# x-OSC_Gloves_v4.net
KiCad netlist of a schematic drawn in EAGLE
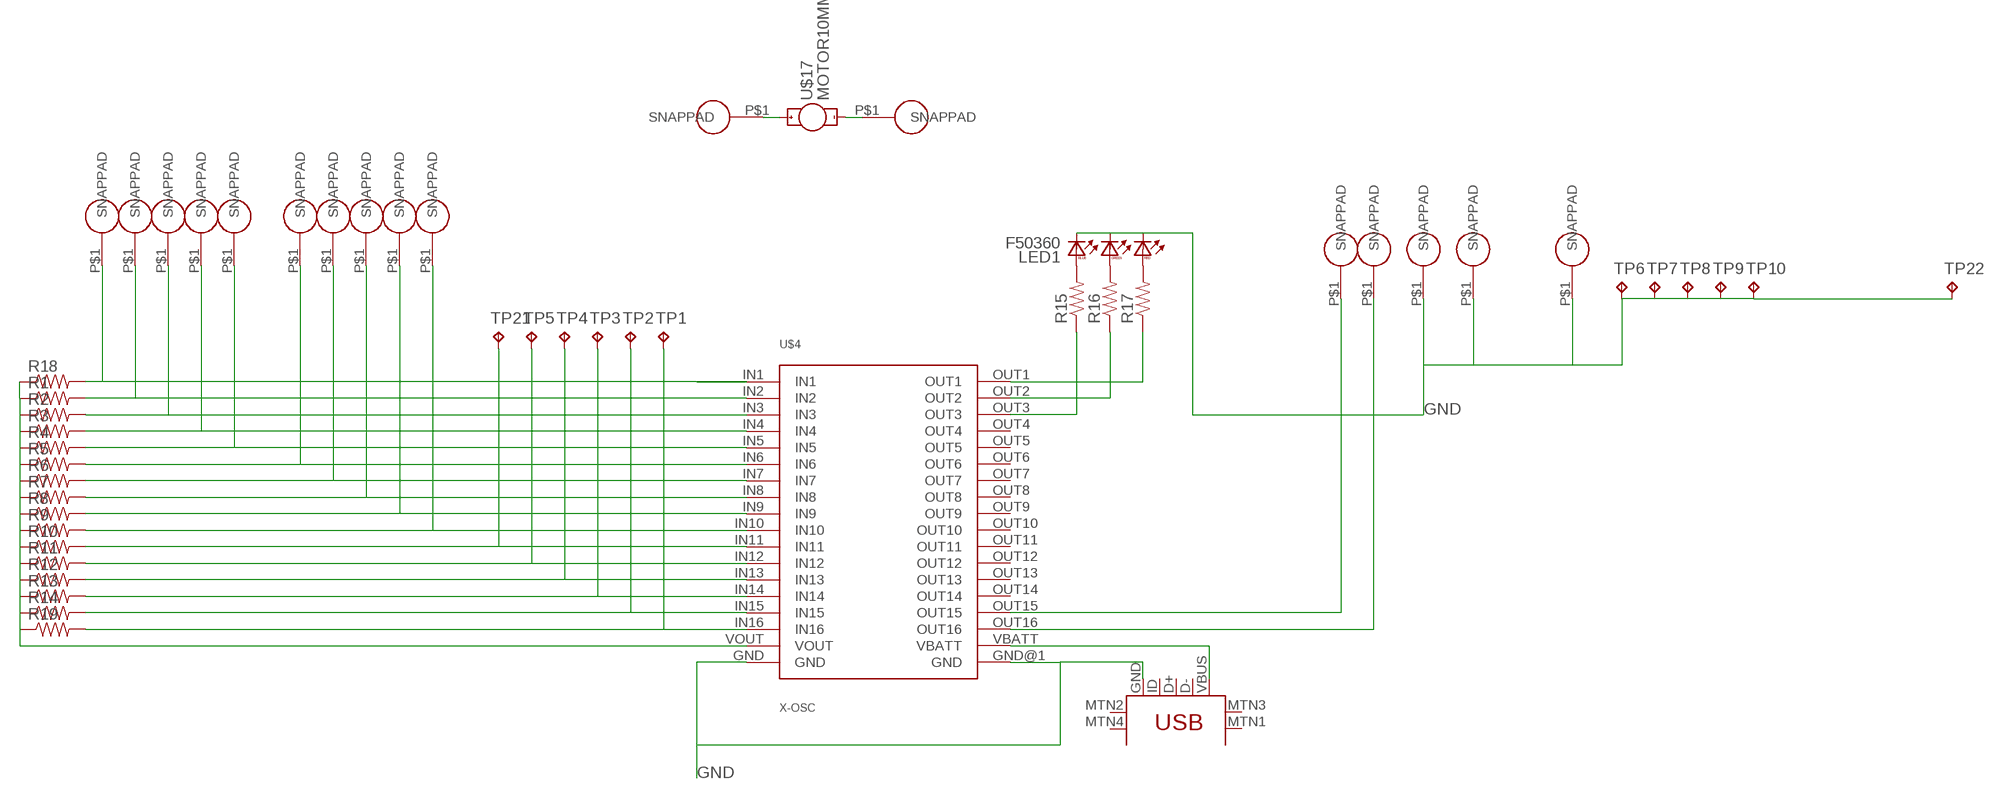
[diagram p0: schematic, sheet 1]

(export (version "E")
  (design (tool "Eeschema 10.0.6"))
  (components
    (comp (ref "LED1")
      (value "F50360")
      (footprint "eagle-import:F50360")
      (libsource (lib "eagle-import") (part "F50360"))
    )
    (comp (ref "R1")
      (value "RESISTOR0805-RES")
      (footprint "eagle-import:0805")
      (libsource (lib "eagle-import") (part "RESISTOR0805-RES"))
    )
    (comp (ref "R2")
      (value "RESISTOR0805-RES")
      (footprint "eagle-import:0805")
      (libsource (lib "eagle-import") (part "RESISTOR0805-RES"))
    )
    (comp (ref "R3")
      (value "RESISTOR0805-RES")
      (footprint "eagle-import:0805")
      (libsource (lib "eagle-import") (part "RESISTOR0805-RES"))
    )
    (comp (ref "R4")
      (value "RESISTOR0805-RES")
      (footprint "eagle-import:0805")
      (libsource (lib "eagle-import") (part "RESISTOR0805-RES"))
    )
    (comp (ref "R5")
      (value "RESISTOR0805-RES")
      (footprint "eagle-import:0805")
      (libsource (lib "eagle-import") (part "RESISTOR0805-RES"))
    )
    (comp (ref "R6")
      (value "RESISTOR0805-RES")
      (footprint "eagle-import:0805")
      (libsource (lib "eagle-import") (part "RESISTOR0805-RES"))
    )
    (comp (ref "R7")
      (value "RESISTOR0805-RES")
      (footprint "eagle-import:0805")
      (libsource (lib "eagle-import") (part "RESISTOR0805-RES"))
    )
    (comp (ref "R8")
      (value "RESISTOR0805-RES")
      (footprint "eagle-import:0805")
      (libsource (lib "eagle-import") (part "RESISTOR0805-RES"))
    )
    (comp (ref "R9")
      (value "RESISTOR0805-RES")
      (footprint "eagle-import:0805")
      (libsource (lib "eagle-import") (part "RESISTOR0805-RES"))
    )
    (comp (ref "R10")
      (value "RESISTOR0805-RES")
      (footprint "eagle-import:0805")
      (libsource (lib "eagle-import") (part "RESISTOR0805-RES"))
    )
    (comp (ref "R11")
      (value "RESISTOR0805-RES")
      (footprint "eagle-import:0805")
      (libsource (lib "eagle-import") (part "RESISTOR0805-RES"))
    )
    (comp (ref "R12")
      (value "RESISTOR0805-RES")
      (footprint "eagle-import:0805")
      (libsource (lib "eagle-import") (part "RESISTOR0805-RES"))
    )
    (comp (ref "R13")
      (value "RESISTOR0805-RES")
      (footprint "eagle-import:0805")
      (libsource (lib "eagle-import") (part "RESISTOR0805-RES"))
    )
    (comp (ref "R14")
      (value "RESISTOR0805-RES")
      (footprint "eagle-import:0805")
      (libsource (lib "eagle-import") (part "RESISTOR0805-RES"))
    )
    (comp (ref "R15")
      (value "RESISTOR0805-RES")
      (footprint "eagle-import:0805")
      (libsource (lib "eagle-import") (part "RESISTOR0805-RES"))
    )
    (comp (ref "R16")
      (value "RESISTOR0805-RES")
      (footprint "eagle-import:0805")
      (libsource (lib "eagle-import") (part "RESISTOR0805-RES"))
    )
    (comp (ref "R17")
      (value "RESISTOR0805-RES")
      (footprint "eagle-import:0805")
      (libsource (lib "eagle-import") (part "RESISTOR0805-RES"))
    )
    (comp (ref "R18")
      (value "RESISTOR0805-RES")
      (footprint "eagle-import:0805")
      (libsource (lib "eagle-import") (part "RESISTOR0805-RES"))
    )
    (comp (ref "R19")
      (value "RESISTOR0805-RES")
      (footprint "eagle-import:0805")
      (libsource (lib "eagle-import") (part "RESISTOR0805-RES"))
    )
    (comp (ref "TP1")
      (value "TPTP20R")
      (footprint "eagle-import:TP20R")
      (libsource (lib "eagle-import") (part "TPTP20R"))
    )
    (comp (ref "TP2")
      (value "TPTP20R")
      (footprint "eagle-import:TP20R")
      (libsource (lib "eagle-import") (part "TPTP20R"))
    )
    (comp (ref "TP3")
      (value "TPTP20R")
      (footprint "eagle-import:TP20R")
      (libsource (lib "eagle-import") (part "TPTP20R"))
    )
    (comp (ref "TP4")
      (value "TPTP20R")
      (footprint "eagle-import:TP20R")
      (libsource (lib "eagle-import") (part "TPTP20R"))
    )
    (comp (ref "TP5")
      (value "TPTP20R")
      (footprint "eagle-import:TP20R")
      (libsource (lib "eagle-import") (part "TPTP20R"))
    )
    (comp (ref "TP6")
      (value "TPTP20R")
      (footprint "eagle-import:TP20R")
      (libsource (lib "eagle-import") (part "TPTP20R"))
    )
    (comp (ref "TP7")
      (value "TPTP20R")
      (footprint "eagle-import:TP20R")
      (libsource (lib "eagle-import") (part "TPTP20R"))
    )
    (comp (ref "TP8")
      (value "TPTP20R")
      (footprint "eagle-import:TP20R")
      (libsource (lib "eagle-import") (part "TPTP20R"))
    )
    (comp (ref "TP9")
      (value "TPTP20R")
      (footprint "eagle-import:TP20R")
      (libsource (lib "eagle-import") (part "TPTP20R"))
    )
    (comp (ref "TP10")
      (value "TPTP20R")
      (footprint "eagle-import:TP20R")
      (libsource (lib "eagle-import") (part "TPTP20R"))
    )
    (comp (ref "TP21")
      (value "TPTP20R")
      (footprint "eagle-import:TP20R")
      (libsource (lib "eagle-import") (part "TPTP20R"))
    )
    (comp (ref "TP22")
      (value "TPTP20R")
      (footprint "eagle-import:TP20R")
      (libsource (lib "eagle-import") (part "TPTP20R"))
    )
    (comp (ref "U$1")
      (value "SNAP-PAD_7MM_ROUND")
      (footprint "eagle-import:SNAP-PAD_7MM_RD")
      (libsource (lib "eagle-import") (part "SNAP-PAD_7MM_ROUND"))
    )
    (comp (ref "U$2")
      (value "SNAP-PAD_7MM_ROUND")
      (footprint "eagle-import:SNAP-PAD_7MM_RD")
      (libsource (lib "eagle-import") (part "SNAP-PAD_7MM_ROUND"))
    )
    (comp (ref "U$3")
      (value "SNAP-PAD_7MM_ROUND")
      (footprint "eagle-import:SNAP-PAD_7MM_RD")
      (libsource (lib "eagle-import") (part "SNAP-PAD_7MM_ROUND"))
    )
    (comp (ref "U$4")
      (value "X-OSC")
      (footprint "eagle-import:X-OSC_SMD")
      (libsource (lib "eagle-import") (part "X-OSC"))
    )
    (comp (ref "U$5")
      (value "USB-MINIB-5PIN")
      (footprint "eagle-import:USB-MINIB")
      (libsource (lib "eagle-import") (part "USB-MINIB-5PIN"))
    )
    (comp (ref "U$6")
      (value "SNAP-PAD_7MM_ROUND")
      (footprint "eagle-import:SNAP-PAD_7MM_RD")
      (libsource (lib "eagle-import") (part "SNAP-PAD_7MM_ROUND"))
    )
    (comp (ref "U$7")
      (value "SNAP-PAD_7MM_ROUND")
      (footprint "eagle-import:SNAP-PAD_7MM_RD")
      (libsource (lib "eagle-import") (part "SNAP-PAD_7MM_ROUND"))
    )
    (comp (ref "U$8")
      (value "SNAP-PAD_7MM_ROUND")
      (footprint "eagle-import:SNAP-PAD_7MM_RD")
      (libsource (lib "eagle-import") (part "SNAP-PAD_7MM_ROUND"))
    )
    (comp (ref "U$9")
      (value "SNAP-PAD_7MM_ROUND")
      (footprint "eagle-import:SNAP-PAD_7MM_RD")
      (libsource (lib "eagle-import") (part "SNAP-PAD_7MM_ROUND"))
    )
    (comp (ref "U$10")
      (value "SNAP-PAD_7MM_ROUND")
      (footprint "eagle-import:SNAP-PAD_7MM_RD")
      (libsource (lib "eagle-import") (part "SNAP-PAD_7MM_ROUND"))
    )
    (comp (ref "U$11")
      (value "SNAP-PAD_7MM_ROUND")
      (footprint "eagle-import:SNAP-PAD_7MM_RD")
      (libsource (lib "eagle-import") (part "SNAP-PAD_7MM_ROUND"))
    )
    (comp (ref "U$13")
      (value "SNAP-PAD_7MM_ROUND")
      (footprint "eagle-import:SNAP-PAD_7MM_RD")
      (libsource (lib "eagle-import") (part "SNAP-PAD_7MM_ROUND"))
    )
    (comp (ref "U$14")
      (value "SNAP-PAD_7MM_ROUND")
      (footprint "eagle-import:SNAP-PAD_7MM_RD")
      (libsource (lib "eagle-import") (part "SNAP-PAD_7MM_ROUND"))
    )
    (comp (ref "U$15")
      (value "SNAP-PAD_7MM_ROUND")
      (footprint "eagle-import:SNAP-PAD_7MM_RD")
      (libsource (lib "eagle-import") (part "SNAP-PAD_7MM_ROUND"))
    )
    (comp (ref "U$16")
      (value "SNAP-PAD_7MM_ROUND")
      (footprint "eagle-import:SNAP-PAD_7MM_RD")
      (libsource (lib "eagle-import") (part "SNAP-PAD_7MM_ROUND"))
    )
    (comp (ref "U$17")
      (value "MOTOR10MM")
      (footprint "eagle-import:VIBE-MOTOR-10MM")
      (libsource (lib "eagle-import") (part "MOTOR10MM"))
    )
    (comp (ref "U$18")
      (value "SNAP-PAD_7MM_ROUND")
      (footprint "eagle-import:SNAP-PAD_7MM_RD")
      (libsource (lib "eagle-import") (part "SNAP-PAD_7MM_ROUND"))
    )
    (comp (ref "U$19")
      (value "SNAP-PAD_7MM_ROUND")
      (footprint "eagle-import:SNAP-PAD_7MM_RD")
      (libsource (lib "eagle-import") (part "SNAP-PAD_7MM_ROUND"))
    )
    (comp (ref "U$20")
      (value "SNAP-PAD_7MM_ROUND")
      (footprint "eagle-import:SNAP-PAD_7MM_RD")
      (libsource (lib "eagle-import") (part "SNAP-PAD_7MM_ROUND"))
    )
    (comp (ref "U$21")
      (value "SNAP-PAD_7MM_ROUND")
      (footprint "eagle-import:SNAP-PAD_7MM_RD")
      (libsource (lib "eagle-import") (part "SNAP-PAD_7MM_ROUND"))
    )
  )
  (nets
    (net (code "1") (name "/GND") (class "Default")
      (node (ref "LED1") (pin "BC") (pinfunction "BC_BC") (pintype "passive"))
      (node (ref "LED1") (pin "GC") (pinfunction "GC_GC") (pintype "passive"))
      (node (ref "LED1") (pin "RC") (pinfunction "RC_RC") (pintype "passive"))
      (node (ref "TP10") (pin "TP") (pinfunction "TP_TP") (pintype "input"))
      (node (ref "TP22") (pin "TP") (pinfunction "TP_TP") (pintype "input"))
      (node (ref "TP6") (pin "TP") (pinfunction "TP_TP") (pintype "input"))
      (node (ref "TP7") (pin "TP") (pinfunction "TP_TP") (pintype "input"))
      (node (ref "TP8") (pin "TP") (pinfunction "TP_TP") (pintype "input"))
      (node (ref "TP9") (pin "TP") (pinfunction "TP_TP") (pintype "input"))
      (node (ref "U$15") (pin "P$1") (pinfunction "SNAPPAD_P$1") (pintype "bidirectional"))
      (node (ref "U$16") (pin "P$1") (pinfunction "SNAPPAD_P$1") (pintype "bidirectional"))
      (node (ref "U$18") (pin "P$1") (pinfunction "SNAPPAD_P$1") (pintype "bidirectional"))
      (node (ref "U$4") (pin "GND") (pinfunction "GND_GND") (pintype "bidirectional"))
      (node (ref "U$4") (pin "GND@1") (pinfunction "GND_GND@1") (pintype "bidirectional"))
      (node (ref "U$5") (pin "GND") (pinfunction "GND_GND") (pintype "bidirectional"))
    )
    (net (code "2") (name "Net-(LED1-PadBA)") (class "Default")
      (node (ref "LED1") (pin "BA") (pinfunction "BA_BA") (pintype "passive"))
      (node (ref "R15") (pin "2") (pinfunction "2_2") (pintype "passive"))
    )
    (net (code "3") (name "Net-(LED1-PadGA)") (class "Default")
      (node (ref "LED1") (pin "GA") (pinfunction "GA_GA") (pintype "passive"))
      (node (ref "R16") (pin "2") (pinfunction "2_2") (pintype "passive"))
    )
    (net (code "4") (name "Net-(LED1-PadRA)") (class "Default")
      (node (ref "LED1") (pin "RA") (pinfunction "RA_RA") (pintype "passive"))
      (node (ref "R17") (pin "2") (pinfunction "2_2") (pintype "passive"))
    )
    (net (code "5") (name "Net-(R1-Pad1)") (class "Default")
      (node (ref "R1") (pin "1") (pinfunction "1_1") (pintype "passive"))
      (node (ref "R10") (pin "1") (pinfunction "1_1") (pintype "passive"))
      (node (ref "R11") (pin "1") (pinfunction "1_1") (pintype "passive"))
      (node (ref "R12") (pin "1") (pinfunction "1_1") (pintype "passive"))
      (node (ref "R13") (pin "1") (pinfunction "1_1") (pintype "passive"))
      (node (ref "R14") (pin "1") (pinfunction "1_1") (pintype "passive"))
      (node (ref "R18") (pin "1") (pinfunction "1_1") (pintype "passive"))
      (node (ref "R19") (pin "1") (pinfunction "1_1") (pintype "passive"))
      (node (ref "R2") (pin "1") (pinfunction "1_1") (pintype "passive"))
      (node (ref "R3") (pin "1") (pinfunction "1_1") (pintype "passive"))
      (node (ref "R4") (pin "1") (pinfunction "1_1") (pintype "passive"))
      (node (ref "R5") (pin "1") (pinfunction "1_1") (pintype "passive"))
      (node (ref "R6") (pin "1") (pinfunction "1_1") (pintype "passive"))
      (node (ref "R7") (pin "1") (pinfunction "1_1") (pintype "passive"))
      (node (ref "R8") (pin "1") (pinfunction "1_1") (pintype "passive"))
      (node (ref "R9") (pin "1") (pinfunction "1_1") (pintype "passive"))
      (node (ref "U$4") (pin "VOUT") (pinfunction "VOUT_VOUT") (pintype "bidirectional"))
    )
    (net (code "6") (name "Net-(R10-Pad2)") (class "Default")
      (node (ref "R10") (pin "2") (pinfunction "2_2") (pintype "passive"))
      (node (ref "TP21") (pin "TP") (pinfunction "TP_TP") (pintype "input"))
      (node (ref "U$4") (pin "IN11") (pinfunction "IN11_IN11") (pintype "bidirectional"))
    )
    (net (code "7") (name "Net-(R11-Pad2)") (class "Default")
      (node (ref "R11") (pin "2") (pinfunction "2_2") (pintype "passive"))
      (node (ref "TP5") (pin "TP") (pinfunction "TP_TP") (pintype "input"))
      (node (ref "U$4") (pin "IN12") (pinfunction "IN12_IN12") (pintype "bidirectional"))
    )
    (net (code "8") (name "Net-(R12-Pad2)") (class "Default")
      (node (ref "R12") (pin "2") (pinfunction "2_2") (pintype "passive"))
      (node (ref "TP4") (pin "TP") (pinfunction "TP_TP") (pintype "input"))
      (node (ref "U$4") (pin "IN13") (pinfunction "IN13_IN13") (pintype "bidirectional"))
    )
    (net (code "9") (name "Net-(R13-Pad2)") (class "Default")
      (node (ref "R13") (pin "2") (pinfunction "2_2") (pintype "passive"))
      (node (ref "TP3") (pin "TP") (pinfunction "TP_TP") (pintype "input"))
      (node (ref "U$4") (pin "IN14") (pinfunction "IN14_IN14") (pintype "bidirectional"))
    )
    (net (code "10") (name "Net-(R14-Pad2)") (class "Default")
      (node (ref "R14") (pin "2") (pinfunction "2_2") (pintype "passive"))
      (node (ref "TP2") (pin "TP") (pinfunction "TP_TP") (pintype "input"))
      (node (ref "U$4") (pin "IN15") (pinfunction "IN15_IN15") (pintype "bidirectional"))
    )
    (net (code "11") (name "Net-(R15-Pad1)") (class "Default")
      (node (ref "R15") (pin "1") (pinfunction "1_1") (pintype "passive"))
      (node (ref "U$4") (pin "OUT3") (pinfunction "OUT3_OUT3") (pintype "bidirectional"))
    )
    (net (code "12") (name "Net-(R16-Pad1)") (class "Default")
      (node (ref "R16") (pin "1") (pinfunction "1_1") (pintype "passive"))
      (node (ref "U$4") (pin "OUT2") (pinfunction "OUT2_OUT2") (pintype "bidirectional"))
    )
    (net (code "13") (name "Net-(R17-Pad1)") (class "Default")
      (node (ref "R17") (pin "1") (pinfunction "1_1") (pintype "passive"))
      (node (ref "U$4") (pin "OUT1") (pinfunction "OUT1_OUT1") (pintype "bidirectional"))
    )
    (net (code "14") (name "Net-(R19-Pad2)") (class "Default")
      (node (ref "R19") (pin "2") (pinfunction "2_2") (pintype "passive"))
      (node (ref "TP1") (pin "TP") (pinfunction "TP_TP") (pintype "input"))
      (node (ref "U$4") (pin "IN16") (pinfunction "IN16_IN16") (pintype "bidirectional"))
    )
    (net (code "15") (name "Net-(U$1-SNAPPAD)") (class "Default")
      (node (ref "R1") (pin "2") (pinfunction "2_2") (pintype "passive"))
      (node (ref "U$1") (pin "P$1") (pinfunction "SNAPPAD_P$1") (pintype "bidirectional"))
      (node (ref "U$4") (pin "IN2") (pinfunction "IN2_IN2") (pintype "bidirectional"))
    )
    (net (code "16") (name "Net-(U$2-SNAPPAD)") (class "Default")
      (node (ref "R2") (pin "2") (pinfunction "2_2") (pintype "passive"))
      (node (ref "U$2") (pin "P$1") (pinfunction "SNAPPAD_P$1") (pintype "bidirectional"))
      (node (ref "U$4") (pin "IN3") (pinfunction "IN3_IN3") (pintype "bidirectional"))
    )
    (net (code "17") (name "Net-(U$3-SNAPPAD)") (class "Default")
      (node (ref "R3") (pin "2") (pinfunction "2_2") (pintype "passive"))
      (node (ref "U$3") (pin "P$1") (pinfunction "SNAPPAD_P$1") (pintype "bidirectional"))
      (node (ref "U$4") (pin "IN4") (pinfunction "IN4_IN4") (pintype "bidirectional"))
    )
    (net (code "18") (name "Net-(U$4-PadVBATT)") (class "Default")
      (node (ref "U$4") (pin "VBATT") (pinfunction "VBATT_VBATT") (pintype "bidirectional"))
      (node (ref "U$5") (pin "VBUS") (pinfunction "VBUS_VBUS") (pintype "bidirectional"))
    )
    (net (code "19") (name "Net-(U$6-SNAPPAD)") (class "Default")
      (node (ref "R4") (pin "2") (pinfunction "2_2") (pintype "passive"))
      (node (ref "U$4") (pin "IN5") (pinfunction "IN5_IN5") (pintype "bidirectional"))
      (node (ref "U$6") (pin "P$1") (pinfunction "SNAPPAD_P$1") (pintype "bidirectional"))
    )
    (net (code "20") (name "Net-(U$7-SNAPPAD)") (class "Default")
      (node (ref "R5") (pin "2") (pinfunction "2_2") (pintype "passive"))
      (node (ref "U$4") (pin "IN6") (pinfunction "IN6_IN6") (pintype "bidirectional"))
      (node (ref "U$7") (pin "P$1") (pinfunction "SNAPPAD_P$1") (pintype "bidirectional"))
    )
    (net (code "21") (name "Net-(U$8-SNAPPAD)") (class "Default")
      (node (ref "R6") (pin "2") (pinfunction "2_2") (pintype "passive"))
      (node (ref "U$4") (pin "IN7") (pinfunction "IN7_IN7") (pintype "bidirectional"))
      (node (ref "U$8") (pin "P$1") (pinfunction "SNAPPAD_P$1") (pintype "bidirectional"))
    )
    (net (code "22") (name "Net-(U$9-SNAPPAD)") (class "Default")
      (node (ref "R7") (pin "2") (pinfunction "2_2") (pintype "passive"))
      (node (ref "U$4") (pin "IN8") (pinfunction "IN8_IN8") (pintype "bidirectional"))
      (node (ref "U$9") (pin "P$1") (pinfunction "SNAPPAD_P$1") (pintype "bidirectional"))
    )
    (net (code "23") (name "Net-(U$10-SNAPPAD)") (class "Default")
      (node (ref "R8") (pin "2") (pinfunction "2_2") (pintype "passive"))
      (node (ref "U$10") (pin "P$1") (pinfunction "SNAPPAD_P$1") (pintype "bidirectional"))
      (node (ref "U$4") (pin "IN9") (pinfunction "IN9_IN9") (pintype "bidirectional"))
    )
    (net (code "24") (name "Net-(U$11-SNAPPAD)") (class "Default")
      (node (ref "R9") (pin "2") (pinfunction "2_2") (pintype "passive"))
      (node (ref "U$11") (pin "P$1") (pinfunction "SNAPPAD_P$1") (pintype "bidirectional"))
      (node (ref "U$4") (pin "IN10") (pinfunction "IN10_IN10") (pintype "bidirectional"))
    )
    (net (code "25") (name "Net-(U$13-SNAPPAD)") (class "Default")
      (node (ref "U$13") (pin "P$1") (pinfunction "SNAPPAD_P$1") (pintype "bidirectional"))
      (node (ref "U$4") (pin "OUT15") (pinfunction "OUT15_OUT15") (pintype "bidirectional"))
    )
    (net (code "26") (name "Net-(U$14-SNAPPAD)") (class "Default")
      (node (ref "U$14") (pin "P$1") (pinfunction "SNAPPAD_P$1") (pintype "bidirectional"))
      (node (ref "U$4") (pin "OUT16") (pinfunction "OUT16_OUT16") (pintype "bidirectional"))
    )
    (net (code "27") (name "Net-(U$19-SNAPPAD)") (class "Default")
      (node (ref "U$17") (pin "+") (pinfunction "+_+") (pintype "bidirectional"))
      (node (ref "U$19") (pin "P$1") (pinfunction "SNAPPAD_P$1") (pintype "bidirectional"))
    )
    (net (code "28") (name "Net-(U$20-SNAPPAD)") (class "Default")
      (node (ref "U$17") (pin "-") (pinfunction "-_-") (pintype "bidirectional"))
      (node (ref "U$20") (pin "P$1") (pinfunction "SNAPPAD_P$1") (pintype "bidirectional"))
    )
    (net (code "29") (name "Net-(U$21-SNAPPAD)") (class "Default")
      (node (ref "R18") (pin "2") (pinfunction "2_2") (pintype "passive"))
      (node (ref "U$21") (pin "P$1") (pinfunction "SNAPPAD_P$1") (pintype "bidirectional"))
      (node (ref "U$4") (pin "IN1") (pinfunction "IN1_IN1") (pintype "bidirectional"))
    )
    (net (code "30") (name "unconnected-(U$4-PadOUT4)") (class "Default")
      (node (ref "U$4") (pin "OUT4") (pinfunction "OUT4_OUT4") (pintype "bidirectional"))
    )
    (net (code "31") (name "unconnected-(U$4-PadOUT5)") (class "Default")
      (node (ref "U$4") (pin "OUT5") (pinfunction "OUT5_OUT5") (pintype "bidirectional"))
    )
    (net (code "32") (name "unconnected-(U$4-PadOUT6)") (class "Default")
      (node (ref "U$4") (pin "OUT6") (pinfunction "OUT6_OUT6") (pintype "bidirectional"))
    )
    (net (code "33") (name "unconnected-(U$4-PadOUT7)") (class "Default")
      (node (ref "U$4") (pin "OUT7") (pinfunction "OUT7_OUT7") (pintype "bidirectional"))
    )
    (net (code "34") (name "unconnected-(U$4-PadOUT8)") (class "Default")
      (node (ref "U$4") (pin "OUT8") (pinfunction "OUT8_OUT8") (pintype "bidirectional"))
    )
    (net (code "35") (name "unconnected-(U$4-PadOUT9)") (class "Default")
      (node (ref "U$4") (pin "OUT9") (pinfunction "OUT9_OUT9") (pintype "bidirectional"))
    )
    (net (code "36") (name "unconnected-(U$4-PadOUT10)") (class "Default")
      (node (ref "U$4") (pin "OUT10") (pinfunction "OUT10_OUT10") (pintype "bidirectional"))
    )
    (net (code "37") (name "unconnected-(U$4-PadOUT11)") (class "Default")
      (node (ref "U$4") (pin "OUT11") (pinfunction "OUT11_OUT11") (pintype "bidirectional"))
    )
    (net (code "38") (name "unconnected-(U$4-PadOUT12)") (class "Default")
      (node (ref "U$4") (pin "OUT12") (pinfunction "OUT12_OUT12") (pintype "bidirectional"))
    )
    (net (code "39") (name "unconnected-(U$4-PadOUT13)") (class "Default")
      (node (ref "U$4") (pin "OUT13") (pinfunction "OUT13_OUT13") (pintype "bidirectional"))
    )
    (net (code "40") (name "unconnected-(U$4-PadOUT14)") (class "Default")
      (node (ref "U$4") (pin "OUT14") (pinfunction "OUT14_OUT14") (pintype "bidirectional"))
    )
    (net (code "41") (name "unconnected-(U$5-MTN1-PadMTN3)") (class "Default")
      (node (ref "U$5") (pin "MTN3") (pinfunction "MTN1_MTN3") (pintype "bidirectional"))
    )
    (net (code "42") (name "unconnected-(U$5-MTN2-PadMTN1)") (class "Default")
      (node (ref "U$5") (pin "MTN1") (pinfunction "MTN2_MTN1") (pintype "bidirectional"))
    )
    (net (code "43") (name "unconnected-(U$5-MTN3-PadMTN2)") (class "Default")
      (node (ref "U$5") (pin "MTN2") (pinfunction "MTN3_MTN2") (pintype "bidirectional"))
    )
    (net (code "44") (name "unconnected-(U$5-PadD+)") (class "Default")
      (node (ref "U$5") (pin "D+") (pinfunction "D+_D+") (pintype "bidirectional"))
    )
    (net (code "45") (name "unconnected-(U$5-PadD-)") (class "Default")
      (node (ref "U$5") (pin "D-") (pinfunction "D-_D-") (pintype "bidirectional"))
    )
    (net (code "46") (name "unconnected-(U$5-PadID)") (class "Default")
      (node (ref "U$5") (pin "ID") (pinfunction "ID_ID") (pintype "bidirectional"))
    )
    (net (code "47") (name "unconnected-(U$5-PadMTN4)") (class "Default")
      (node (ref "U$5") (pin "MTN4") (pinfunction "MTN4_MTN4") (pintype "bidirectional"))
    )
  )
)
